# Buck_Converter.net
KiCad netlist of a schematic drawn in Altium Designer
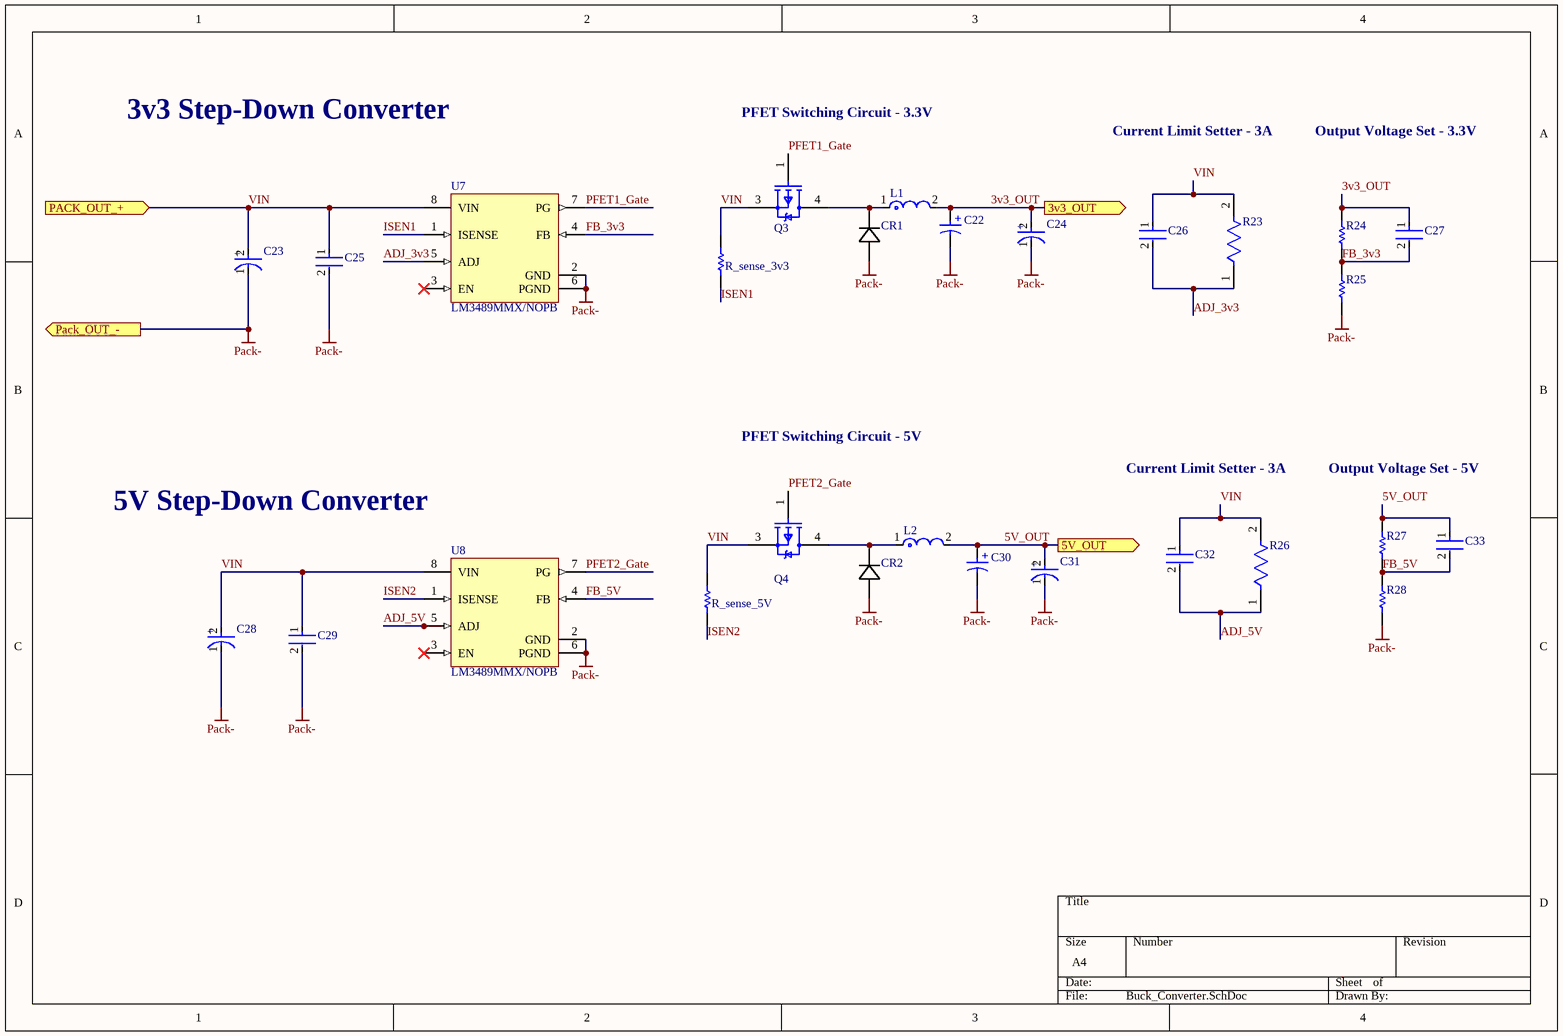
[diagram p0: Buck_Converter.SchDoc]

(export (version "E")
  (design (tool "Eeschema 10.0.6"))
  (components
    (comp (ref "C22")
      (value "865080545012")
      (footprint "WCAP-ASLI_D6.3H7.7")
      (description "865080545012 Cap Aluminum Lytic 100uF 35V 20% (6.3 X 7.7mm) SMD 300mA 2000h 105C T/R")
      (fields (field (name "TOLERANCE") "20%"))
      (libsource (lib "Altium Content Vault") (part "Capacitor_Polarized"))
    )
    (comp (ref "C23")
      (value "EEEFK1H220P")
      (footprint "FP-FKD-MFG")
      (description "CAP ALUM 22UF 20% 50V SMD")
      (fields (field (name "TOLERANCE") "20%") (field (name "VOLTAGE") "50V"))
      (libsource (lib "Altium Content Vault") (part "203bc49f2ac43e59fd269a8c329ed05"))
    )
    (comp (ref "C24")
      (value "EEE-FK1H100UR")
      (footprint "FP-FKC-MFG")
      (description "CAP ALUM 10UF 20% 50V SMD")
      (fields (field (name "TOLERANCE") "20%") (field (name "VOLTAGE") "50V"))
      (libsource (lib "Altium Content Vault") (part "a00bbbee19879c290e62620ae7e47b1"))
    )
    (comp (ref "C25")
      (value "C0603C104K5RACTU")
      (footprint "FP-C0603C-CF-MFG")
      (description "CAP CER 0.1UF 50V X7R 0603")
      (fields (field (name "TOLERANCE") "0.1") (field (name "MANUFACTURER") "KEMET"))
      (libsource (lib "Altium Content Vault") (part "b4654b650e69147ec39a6b967a45e02"))
    )
    (comp (ref "C26")
      (value "C0603C104M5RACAUTO")
      (footprint "FP-C0603C-CF-MFG")
      (description "C0603 0.10 μF X7R 30ppm/°C 20.00% 50 V")
      (fields (field (name "MANUFACTURER") "KEMET") (field (name "TOLERANCE") "0.2"))
      (libsource (lib "Altium Content Vault") (part "b4654b650e69147ec39a6b967a45e02"))
    )
    (comp (ref "C27")
      (value "C0603C101J5GACTU")
      (footprint "FP-C0603C-CF-MFG")
      (description "CAP CER 100PF 50V C0G/NP0 0603")
      (fields (field (name "TOLERANCE") "0.05") (field (name "MANUFACTURER") "KEMET"))
      (libsource (lib "Altium Content Vault") (part "b4654b650e69147ec39a6b967a45e02"))
    )
    (comp (ref "C28")
      (value "EEEFK1H220P")
      (footprint "FP-FKD-MFG")
      (description "CAP ALUM 22UF 20% 50V SMD")
      (fields (field (name "TOLERANCE") "20%") (field (name "VOLTAGE") "50V"))
      (libsource (lib "Altium Content Vault") (part "203bc49f2ac43e59fd269a8c329ed05"))
    )
    (comp (ref "C29")
      (value "C0603C104K5RACTU")
      (footprint "FP-C0603C-CF-MFG")
      (description "CAP CER 0.1UF 50V X7R 0603")
      (fields (field (name "TOLERANCE") "0.1") (field (name "MANUFACTURER") "KEMET"))
      (libsource (lib "Altium Content Vault") (part "b4654b650e69147ec39a6b967a45e02"))
    )
    (comp (ref "C30")
      (value "865080545012")
      (footprint "WCAP-ASLI_D6.3H7.7")
      (description "865080545012 Cap Aluminum Lytic 100uF 35V 20% (6.3 X 7.7mm) SMD 300mA 2000h 105C T/R")
      (fields (field (name "TOLERANCE") "20%"))
      (libsource (lib "Altium Content Vault") (part "Capacitor_Polarized"))
    )
    (comp (ref "C31")
      (value "EEE-FK1H100UR")
      (footprint "FP-FKC-MFG")
      (description "CAP ALUM 10UF 20% 50V SMD")
      (fields (field (name "TOLERANCE") "20%") (field (name "VOLTAGE") "50V"))
      (libsource (lib "Altium Content Vault") (part "a00bbbee19879c290e62620ae7e47b1"))
    )
    (comp (ref "C32")
      (value "C0603C104M5RACAUTO")
      (footprint "FP-C0603C-CF-MFG")
      (description "C0603 0.10 μF X7R 30ppm/°C 20.00% 50 V")
      (fields (field (name "MANUFACTURER") "KEMET") (field (name "TOLERANCE") "0.2"))
      (libsource (lib "Altium Content Vault") (part "b4654b650e69147ec39a6b967a45e02"))
    )
    (comp (ref "C33")
      (value "C0603C101J5GACTU")
      (footprint "FP-C0603C-CF-MFG")
      (description "CAP CER 100PF 50V C0G/NP0 0603")
      (fields (field (name "TOLERANCE") "0.05") (field (name "MANUFACTURER") "KEMET"))
      (libsource (lib "Altium Content Vault") (part "b4654b650e69147ec39a6b967a45e02"))
    )
    (comp (ref "CR1")
      (value "B340AE-13")
      (footprint "CR_SMA_320-340AE_DIO")
      (description "No Description Available")
      (libsource (lib "B340AE-13") (part "B340AE-13"))
    )
    (comp (ref "CR2")
      (value "B340AE-13")
      (footprint "CR_SMA_320-340AE_DIO")
      (description "No Description Available")
      (libsource (lib "B340AE-13") (part "B340AE-13"))
    )
    (comp (ref "L1")
      (value "1217AS-H-150M=P3")
      (footprint "FP-DEM8045C-MFG")
      (description "Shielded Wirewound Inductor 15uH 20% 3500mA 0.0528Ω SMD")
      (fields (field (name "TOLERANCE") "20%"))
      (libsource (lib "Altium Content Vault") (part "4cc4b267dca4c8e51f7102f422741d8"))
    )
    (comp (ref "L2")
      (value "1217AS-H-150M=P3")
      (footprint "FP-DEM8045C-MFG")
      (description "Shielded Wirewound Inductor 15uH 20% 3500mA 0.0528Ω SMD")
      (fields (field (name "TOLERANCE") "20%"))
      (libsource (lib "Altium Content Vault") (part "4cc4b267dca4c8e51f7102f422741d8"))
    )
    (comp (ref "Q3")
      (value "IRFR9024NTRPBF")
      (footprint "FP-PG-TO252-3-MFG")
      (description "MOSFET P-CH 55V 11A DPAK")
      (libsource (lib "Altium Content Vault") (part "aefb72304981996cf01338ed7b62555"))
    )
    (comp (ref "Q4")
      (value "IRFR9024NTRPBF")
      (footprint "FP-PG-TO252-3-MFG")
      (description "MOSFET P-CH 55V 11A DPAK")
      (libsource (lib "Altium Content Vault") (part "aefb72304981996cf01338ed7b62555"))
    )
    (comp (ref "R23")
      (value "RMCF0603FT182K")
      (footprint "FP-RMCF0603-MFG")
      (description "RES 182K OHM 1% 1/10W 0603")
      (fields (field (name "TOLERANCE") "1%"))
      (libsource (lib "Altium Content Vault") (part "1029c3af85768c4190bb7ad29bc67b5"))
    )
    (comp (ref "R24")
      (value "ERA3AEB333V")
      (footprint "RESC1608X55X30ML20T20")
      (fields (field (name "MANUFACTURER") "Panasonic"))
      (libsource (lib "Altium Content Vault") (part "RES"))
    )
    (comp (ref "R25")
      (value "ERJ-3EKF2002V")
      (footprint "RESC1608X55X30ML15T15")
      (fields (field (name "MANUFACTURER") "Panasonic"))
      (libsource (lib "Altium Content Vault") (part "RES"))
    )
    (comp (ref "R26")
      (value "RMCF0603FT182K")
      (footprint "FP-RMCF0603-MFG")
      (description "RES 182K OHM 1% 1/10W 0603")
      (fields (field (name "TOLERANCE") "1%"))
      (libsource (lib "Altium Content Vault") (part "1029c3af85768c4190bb7ad29bc67b5"))
    )
    (comp (ref "R27")
      (value "ERA3AEB333V")
      (footprint "RESC1608X55X30ML20T20")
      (fields (field (name "MANUFACTURER") "Panasonic"))
      (libsource (lib "Altium Content Vault") (part "RES"))
    )
    (comp (ref "R28")
      (value "CRCW060311K0FKEA")
      (footprint "RESC1609X50X30ML10T20")
      (fields (field (name "MANUFACTURER") "Vishay Dale"))
      (libsource (lib "Altium Content Vault") (part "RES"))
    )
    (comp (ref "R_sense_3v3")
      (value "RL1220S-R15-F")
      (footprint "RESC2013X50X40LL20T20")
      (fields (field (name "MANUFACTURER") "Susumu"))
      (libsource (lib "Altium Content Vault") (part "RES"))
    )
    (comp (ref "R_sense_5V")
      (value "RL1220S-R15-F")
      (footprint "RESC2013X50X40LL20T20")
      (fields (field (name "MANUFACTURER") "Susumu"))
      (libsource (lib "Altium Content Vault") (part "RES"))
    )
    (comp (ref "U7")
      (value "LM3489MMX/NOPB")
      (footprint "DGK0008A_N")
      (description "Hysteretic PFET Buck Controller with Enable Pin, 8-pin MSOP, Pb-Free")
      (fields (field (name "MANUFACTURER") "Texas Instruments"))
      (libsource (lib "Altium Content Vault") (part "PM-REG-LM3489MM"))
    )
    (comp (ref "U8")
      (value "LM3489MMX/NOPB")
      (footprint "DGK0008A_N")
      (description "Hysteretic PFET Buck Controller with Enable Pin, 8-pin MSOP, Pb-Free")
      (fields (field (name "MANUFACTURER") "Texas Instruments"))
      (libsource (lib "Altium Content Vault") (part "PM-REG-LM3489MM"))
    )
  )
  (nets
    (net (code "1") (name "/3v3_OUT") (class "Default")
      (node (ref "C22") (pin "1") (pinfunction "P_1") (pintype "passive"))
      (node (ref "C24") (pin "2") (pinfunction "A_2") (pintype "passive"))
      (node (ref "C27") (pin "1") (pinfunction "1_1") (pintype "passive"))
      (node (ref "L1") (pin "2") (pinfunction "2_2") (pintype "passive"))
      (node (ref "R24") (pin "2") (pinfunction "2_2") (pintype "passive"))
    )
    (net (code "2") (name "/5V_OUT") (class "Default")
      (node (ref "C30") (pin "1") (pinfunction "P_1") (pintype "passive"))
      (node (ref "C31") (pin "2") (pinfunction "A_2") (pintype "passive"))
      (node (ref "C33") (pin "1") (pinfunction "1_1") (pintype "passive"))
      (node (ref "L2") (pin "2") (pinfunction "2_2") (pintype "passive"))
      (node (ref "R27") (pin "2") (pinfunction "2_2") (pintype "passive"))
    )
    (net (code "3") (name "/ADJ_3v3") (class "Default")
      (node (ref "C26") (pin "2") (pinfunction "2_2") (pintype "passive"))
      (node (ref "R23") (pin "1") (pinfunction "1_1") (pintype "passive"))
      (node (ref "U7") (pin "5") (pinfunction "ADJ_5") (pintype "input"))
    )
    (net (code "4") (name "/ADJ_5V") (class "Default")
      (node (ref "C32") (pin "2") (pinfunction "2_2") (pintype "passive"))
      (node (ref "R26") (pin "1") (pinfunction "1_1") (pintype "passive"))
      (node (ref "U8") (pin "5") (pinfunction "ADJ_5") (pintype "input"))
    )
    (net (code "5") (name "/FB_3v3") (class "Default")
      (node (ref "C27") (pin "2") (pinfunction "2_2") (pintype "passive"))
      (node (ref "R24") (pin "1") (pinfunction "1_1") (pintype "passive"))
      (node (ref "R25") (pin "2") (pinfunction "2_2") (pintype "passive"))
      (node (ref "U7") (pin "4") (pinfunction "FB_4") (pintype "input"))
    )
    (net (code "6") (name "/FB_5V") (class "Default")
      (node (ref "C33") (pin "2") (pinfunction "2_2") (pintype "passive"))
      (node (ref "R27") (pin "1") (pinfunction "1_1") (pintype "passive"))
      (node (ref "R28") (pin "2") (pinfunction "2_2") (pintype "passive"))
      (node (ref "U8") (pin "4") (pinfunction "FB_4") (pintype "input"))
    )
    (net (code "7") (name "/ISEN1") (class "Default")
      (node (ref "R_sense_3v3") (pin "2") (pinfunction "2_2") (pintype "passive"))
      (node (ref "U7") (pin "1") (pinfunction "ISENSE_1") (pintype "input"))
    )
    (net (code "8") (name "/ISEN2") (class "Default")
      (node (ref "R_sense_5V") (pin "2") (pinfunction "2_2") (pintype "passive"))
      (node (ref "U8") (pin "1") (pinfunction "ISENSE_1") (pintype "input"))
    )
    (net (code "9") (name "/PFET1_Gate") (class "Default")
      (node (ref "Q3") (pin "1") (pinfunction "GATE_1") (pintype "passive"))
      (node (ref "U7") (pin "7") (pinfunction "PG_7") (pintype "output"))
    )
    (net (code "10") (name "/PFET2_Gate") (class "Default")
      (node (ref "Q4") (pin "1") (pinfunction "GATE_1") (pintype "passive"))
      (node (ref "U8") (pin "7") (pinfunction "PG_7") (pintype "output"))
    )
    (net (code "11") (name "/VIN") (class "Default")
      (node (ref "C23") (pin "2") (pinfunction "A_2") (pintype "passive"))
      (node (ref "C25") (pin "1") (pinfunction "1_1") (pintype "passive"))
      (node (ref "C26") (pin "1") (pinfunction "1_1") (pintype "passive"))
      (node (ref "C28") (pin "2") (pinfunction "A_2") (pintype "passive"))
      (node (ref "C29") (pin "1") (pinfunction "1_1") (pintype "passive"))
      (node (ref "C32") (pin "1") (pinfunction "1_1") (pintype "passive"))
      (node (ref "Q3") (pin "3") (pinfunction "SOURCE_3") (pintype "passive"))
      (node (ref "Q4") (pin "3") (pinfunction "SOURCE_3") (pintype "passive"))
      (node (ref "R23") (pin "2") (pinfunction "2_2") (pintype "passive"))
      (node (ref "R26") (pin "2") (pinfunction "2_2") (pintype "passive"))
      (node (ref "R_sense_3v3") (pin "1") (pinfunction "1_1") (pintype "passive"))
      (node (ref "R_sense_5V") (pin "1") (pinfunction "1_1") (pintype "passive"))
      (node (ref "U7") (pin "8") (pinfunction "VIN_8") (pintype "power_in"))
      (node (ref "U8") (pin "8") (pinfunction "VIN_8") (pintype "power_in"))
    )
    (net (code "12") (name "Net-(Q3-DRAIN)") (class "Default")
      (node (ref "CR1") (pin "1") (pinfunction "1_1") (pintype "passive"))
      (node (ref "L1") (pin "1") (pinfunction "1_1") (pintype "passive"))
      (node (ref "Q3") (pin "4") (pinfunction "DRAIN_4") (pintype "passive"))
    )
    (net (code "13") (name "Net-(Q4-DRAIN)") (class "Default")
      (node (ref "CR2") (pin "1") (pinfunction "1_1") (pintype "passive"))
      (node (ref "L2") (pin "1") (pinfunction "1_1") (pintype "passive"))
      (node (ref "Q4") (pin "4") (pinfunction "DRAIN_4") (pintype "passive"))
    )
    (net (code "14") (name "Pack-") (class "Default")
      (node (ref "C22") (pin "2") (pinfunction "N_2") (pintype "passive"))
      (node (ref "C23") (pin "1") (pinfunction "C_1") (pintype "passive"))
      (node (ref "C24") (pin "1") (pinfunction "C_1") (pintype "passive"))
      (node (ref "C25") (pin "2") (pinfunction "2_2") (pintype "passive"))
      (node (ref "C28") (pin "1") (pinfunction "C_1") (pintype "passive"))
      (node (ref "C29") (pin "2") (pinfunction "2_2") (pintype "passive"))
      (node (ref "C30") (pin "2") (pinfunction "N_2") (pintype "passive"))
      (node (ref "C31") (pin "1") (pinfunction "C_1") (pintype "passive"))
      (node (ref "CR1") (pin "2") (pinfunction "2_2") (pintype "passive"))
      (node (ref "CR2") (pin "2") (pinfunction "2_2") (pintype "passive"))
      (node (ref "R25") (pin "1") (pinfunction "1_1") (pintype "passive"))
      (node (ref "R28") (pin "1") (pinfunction "1_1") (pintype "passive"))
      (node (ref "U7") (pin "2") (pinfunction "GND_2") (pintype "power_in"))
      (node (ref "U7") (pin "6") (pinfunction "PGND_6") (pintype "power_in"))
      (node (ref "U8") (pin "2") (pinfunction "GND_2") (pintype "power_in"))
      (node (ref "U8") (pin "6") (pinfunction "PGND_6") (pintype "power_in"))
    )
    (net (code "15") (name "unconnected-(U7-EN-Pad3)") (class "Default")
      (node (ref "U7") (pin "3") (pinfunction "EN_3") (pintype "input+no_connect"))
    )
    (net (code "16") (name "unconnected-(U8-EN-Pad3)") (class "Default")
      (node (ref "U8") (pin "3") (pinfunction "EN_3") (pintype "input+no_connect"))
    )
  )
)
